# Ventouse.net
KiCad netlist of a schematic drawn in EAGLE
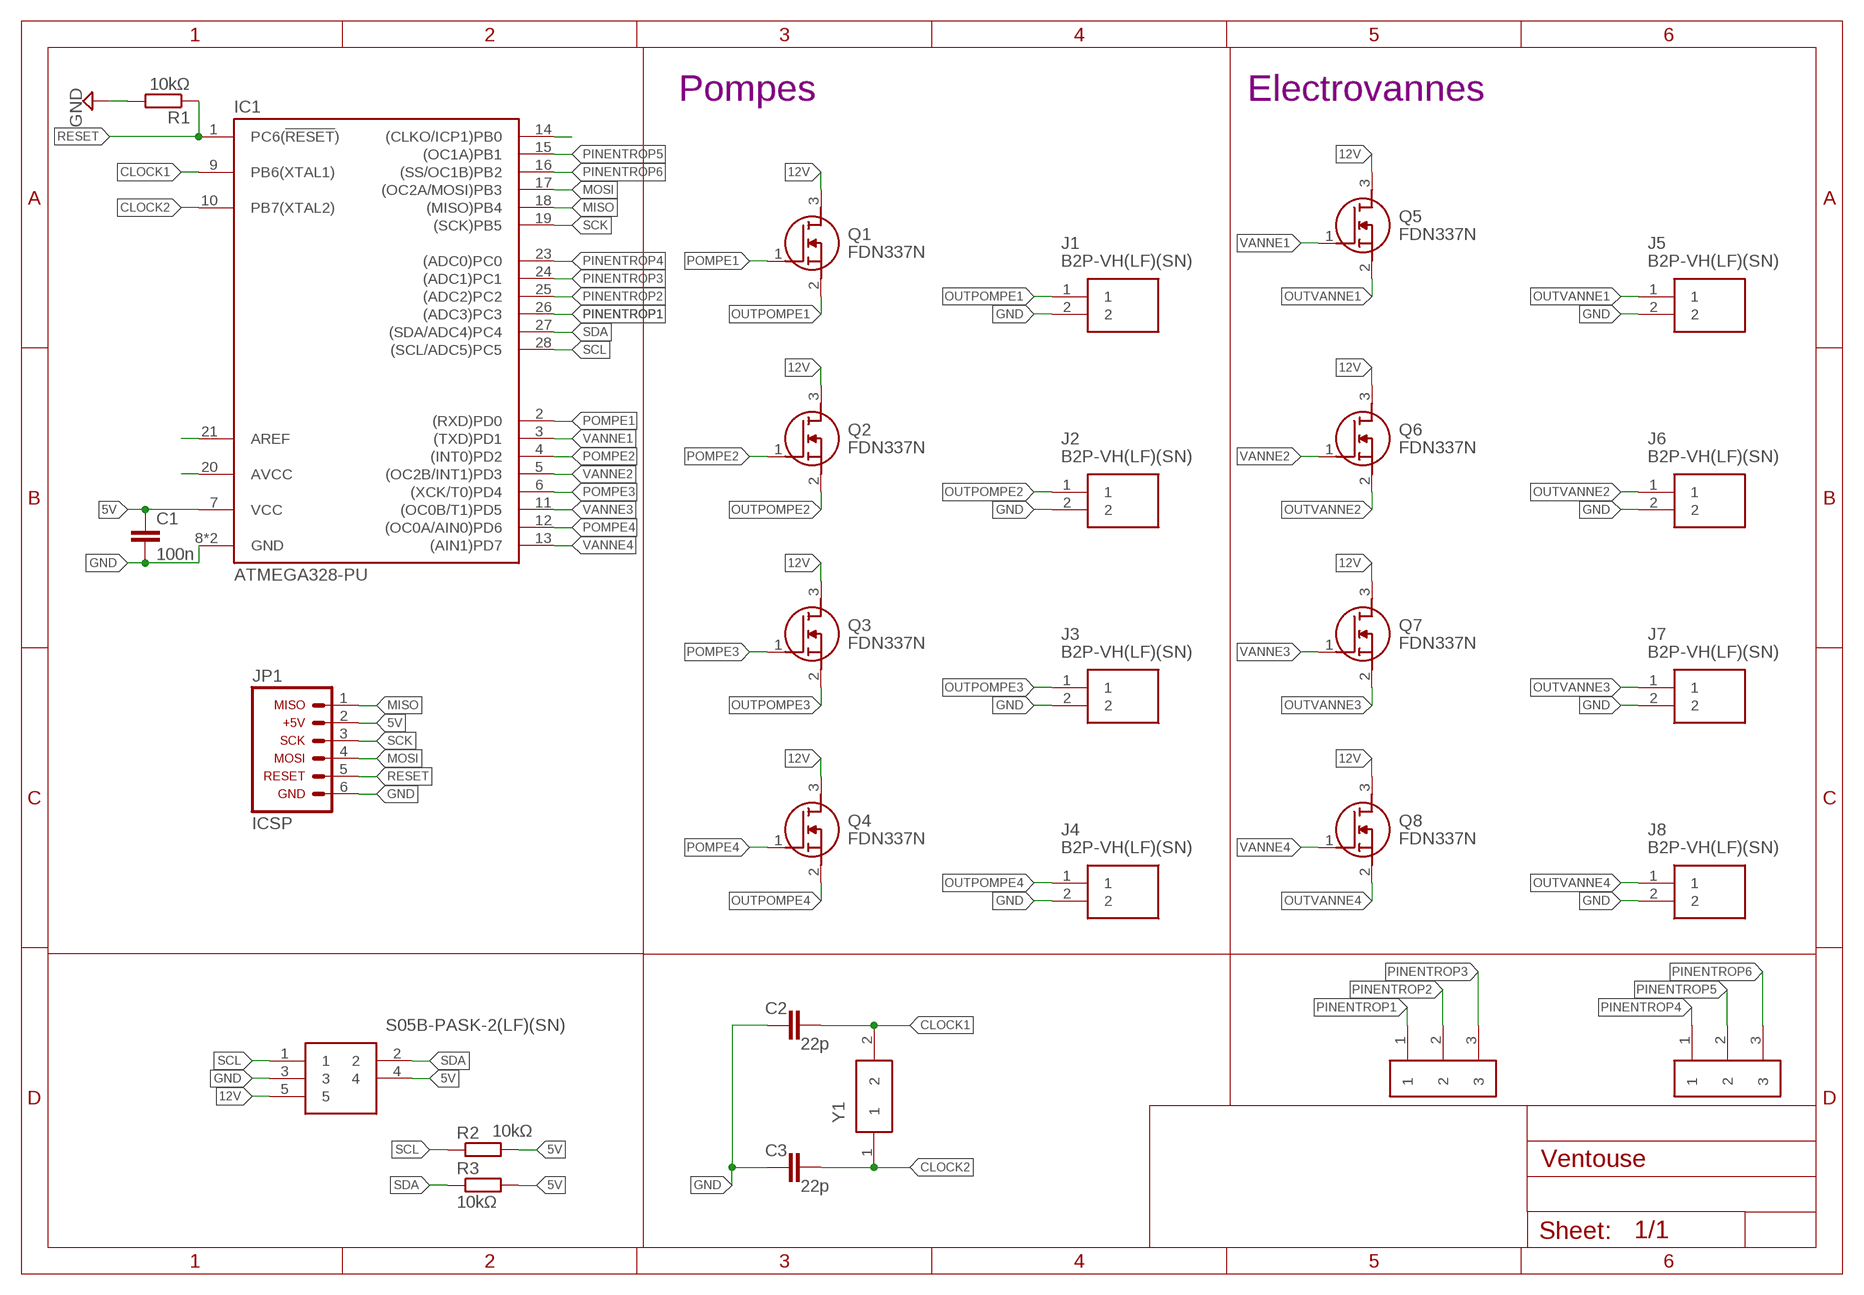
[diagram p0: schematic, sheet 1]

(export (version "E")
  (design (tool "Eeschema 10.0.6"))
  (components
    (comp (ref "C1")
      (value "100n")
      (footprint "eagle-import:C0805")
      (libsource (lib "eagle-import") (part "C-EUC0805"))
    )
    (comp (ref "C2")
      (value "22p")
      (footprint "eagle-import:C0805")
      (libsource (lib "eagle-import") (part "C-EUC0805"))
    )
    (comp (ref "C3")
      (value "22p")
      (footprint "eagle-import:C0805")
      (libsource (lib "eagle-import") (part "C-EUC0805"))
    )
    (comp (ref "IC1")
      (value "ATMEGA328-PU")
      (footprint "eagle-import:DIL28")
      (fields (field (name "MF") "Microchip Technology"))
      (libsource (lib "eagle-import") (part "ATMEGA328-PU"))
    )
    (comp (ref "J1")
      (value "B2P-VH(LF)(SN)")
      (footprint "eagle-import:SHDR2W114P0X396_1X2_786X850X94")
      (fields (field (name "RS_PART_NUMBER") "8201147P"))
      (libsource (lib "eagle-import") (part "B2P-VH(LF)(SN)"))
    )
    (comp (ref "J2")
      (value "B2P-VH(LF)(SN)")
      (footprint "eagle-import:SHDR2W114P0X396_1X2_786X850X94")
      (fields (field (name "RS_PART_NUMBER") "8201147P"))
      (libsource (lib "eagle-import") (part "B2P-VH(LF)(SN)"))
    )
    (comp (ref "J3")
      (value "B2P-VH(LF)(SN)")
      (footprint "eagle-import:SHDR2W114P0X396_1X2_786X850X94")
      (fields (field (name "RS_PART_NUMBER") "8201147P"))
      (libsource (lib "eagle-import") (part "B2P-VH(LF)(SN)"))
    )
    (comp (ref "J4")
      (value "B2P-VH(LF)(SN)")
      (footprint "eagle-import:SHDR2W114P0X396_1X2_786X850X94")
      (fields (field (name "RS_PART_NUMBER") "8201147P"))
      (libsource (lib "eagle-import") (part "B2P-VH(LF)(SN)"))
    )
    (comp (ref "J5")
      (value "B2P-VH(LF)(SN)")
      (footprint "eagle-import:SHDR2W114P0X396_1X2_786X850X94")
      (fields (field (name "RS_PART_NUMBER") "8201147P"))
      (libsource (lib "eagle-import") (part "B2P-VH(LF)(SN)"))
    )
    (comp (ref "J6")
      (value "B2P-VH(LF)(SN)")
      (footprint "eagle-import:SHDR2W114P0X396_1X2_786X850X94")
      (fields (field (name "RS_PART_NUMBER") "8201147P"))
      (libsource (lib "eagle-import") (part "B2P-VH(LF)(SN)"))
    )
    (comp (ref "J7")
      (value "B2P-VH(LF)(SN)")
      (footprint "eagle-import:SHDR2W114P0X396_1X2_786X850X94")
      (fields (field (name "RS_PART_NUMBER") "8201147P"))
      (libsource (lib "eagle-import") (part "B2P-VH(LF)(SN)"))
    )
    (comp (ref "J8")
      (value "B2P-VH(LF)(SN)")
      (footprint "eagle-import:SHDR2W114P0X396_1X2_786X850X94")
      (fields (field (name "RS_PART_NUMBER") "8201147P"))
      (libsource (lib "eagle-import") (part "B2P-VH(LF)(SN)"))
    )
    (comp (ref "JP1")
      (value "ARDUINO_CONN-ICSP")
      (footprint "eagle-import:CONN-2X03")
      (libsource (lib "eagle-import") (part "ARDUINO_CONN-ICSP"))
    )
    (comp (ref "Q1")
      (value "FDN337N")
      (footprint "eagle-import:SOT95P237X112-3N")
      (fields (field (name "MOUSER_PART_NUMBER") "512-FDN337N") (field (name "RS_PART_NUMBER") "6710429P"))
      (libsource (lib "eagle-import") (part "FDN337N"))
    )
    (comp (ref "Q2")
      (value "FDN337N")
      (footprint "eagle-import:SOT95P237X112-3N")
      (fields (field (name "MOUSER_PART_NUMBER") "512-FDN337N") (field (name "RS_PART_NUMBER") "6710429P"))
      (libsource (lib "eagle-import") (part "FDN337N"))
    )
    (comp (ref "Q3")
      (value "FDN337N")
      (footprint "eagle-import:SOT95P237X112-3N")
      (fields (field (name "MOUSER_PART_NUMBER") "512-FDN337N") (field (name "RS_PART_NUMBER") "6710429P"))
      (libsource (lib "eagle-import") (part "FDN337N"))
    )
    (comp (ref "Q4")
      (value "FDN337N")
      (footprint "eagle-import:SOT95P237X112-3N")
      (fields (field (name "MOUSER_PART_NUMBER") "512-FDN337N") (field (name "RS_PART_NUMBER") "6710429P"))
      (libsource (lib "eagle-import") (part "FDN337N"))
    )
    (comp (ref "Q5")
      (value "FDN337N")
      (footprint "eagle-import:SOT95P237X112-3N")
      (fields (field (name "MOUSER_PART_NUMBER") "512-FDN337N") (field (name "RS_PART_NUMBER") "6710429P"))
      (libsource (lib "eagle-import") (part "FDN337N"))
    )
    (comp (ref "Q6")
      (value "FDN337N")
      (footprint "eagle-import:SOT95P237X112-3N")
      (fields (field (name "MOUSER_PART_NUMBER") "512-FDN337N") (field (name "RS_PART_NUMBER") "6710429P"))
      (libsource (lib "eagle-import") (part "FDN337N"))
    )
    (comp (ref "Q7")
      (value "FDN337N")
      (footprint "eagle-import:SOT95P237X112-3N")
      (fields (field (name "MOUSER_PART_NUMBER") "512-FDN337N") (field (name "RS_PART_NUMBER") "6710429P"))
      (libsource (lib "eagle-import") (part "FDN337N"))
    )
    (comp (ref "Q8")
      (value "FDN337N")
      (footprint "eagle-import:SOT95P237X112-3N")
      (fields (field (name "MOUSER_PART_NUMBER") "512-FDN337N") (field (name "RS_PART_NUMBER") "6710429P"))
      (libsource (lib "eagle-import") (part "FDN337N"))
    )
    (comp (ref "R1")
      (value "10kΩ")
      (footprint "eagle-import:R0805")
      (libsource (lib "eagle-import") (part "R-EU_R0805"))
    )
    (comp (ref "R2")
      (value "10kΩ")
      (footprint "eagle-import:R0805")
      (libsource (lib "eagle-import") (part "R-EU_R0805"))
    )
    (comp (ref "R3")
      (value "10kΩ")
      (footprint "eagle-import:R0805")
      (libsource (lib "eagle-import") (part "R-EU_R0805"))
    )
    (comp (ref "SCL")
      (value "S05B-PASK-2(LF)(SN)")
      (footprint "eagle-import:S05B-PASK-2(LF)(SN)")
      (libsource (lib "eagle-import") (part "S05B-PASK-2(LF)(SN)"))
    )
    (comp (ref "U$1")
      (value "HEADER3PIN")
      (footprint "eagle-import:HEADER3PINFOOTPRINT")
      (libsource (lib "eagle-import") (part "HEADER3PIN"))
    )
    (comp (ref "U$2")
      (value "HEADER3PIN")
      (footprint "eagle-import:HEADER3PINFOOTPRINT")
      (libsource (lib "eagle-import") (part "HEADER3PIN"))
    )
    (comp (ref "Y1")
      (value "XRCHA16M000F0A01R0")
      (footprint "eagle-import:XRCHA")
      (fields
        (field (name "MOUSER_PART_NUMBER") "81-XRCHA16M000F0A1R0")
        (field (name "RS_PART_NUMBER") "1446622")
      )
      (libsource (lib "eagle-import") (part "XRCHA16M000F0A01R0"))
    )
  )
  (nets
    (net (code "1") (name "5V") (class "Default")
      (node (ref "C1") (pin "1") (pinfunction "1_1") (pintype "passive"))
      (node (ref "IC1") (pin "7") (pinfunction "VCC_7") (pintype "power_in"))
      (node (ref "JP1") (pin "2") (pinfunction "2_2") (pintype "passive"))
      (node (ref "R2") (pin "2") (pinfunction "2_2") (pintype "passive"))
      (node (ref "R3") (pin "2") (pinfunction "2_2") (pintype "passive"))
      (node (ref "SCL") (pin "4") (pinfunction "4_4") (pintype "bidirectional"))
    )
    (net (code "2") (name "12V") (class "Default")
      (node (ref "Q1") (pin "3") (pinfunction "D_3") (pintype "bidirectional"))
      (node (ref "Q2") (pin "3") (pinfunction "D_3") (pintype "bidirectional"))
      (node (ref "Q3") (pin "3") (pinfunction "D_3") (pintype "bidirectional"))
      (node (ref "Q4") (pin "3") (pinfunction "D_3") (pintype "bidirectional"))
      (node (ref "Q5") (pin "3") (pinfunction "D_3") (pintype "bidirectional"))
      (node (ref "Q6") (pin "3") (pinfunction "D_3") (pintype "bidirectional"))
      (node (ref "Q7") (pin "3") (pinfunction "D_3") (pintype "bidirectional"))
      (node (ref "Q8") (pin "3") (pinfunction "D_3") (pintype "bidirectional"))
      (node (ref "SCL") (pin "5") (pinfunction "5_5") (pintype "bidirectional"))
    )
    (net (code "3") (name "CLOCK1") (class "Default")
      (node (ref "C2") (pin "2") (pinfunction "2_2") (pintype "passive"))
      (node (ref "IC1") (pin "9") (pinfunction "PB6(XTAL1)_9") (pintype "bidirectional"))
      (node (ref "Y1") (pin "2") (pinfunction "2_2") (pintype "bidirectional"))
    )
    (net (code "4") (name "CLOCK2") (class "Default")
      (node (ref "C3") (pin "2") (pinfunction "2_2") (pintype "passive"))
      (node (ref "IC1") (pin "10") (pinfunction "PB7(XTAL2)_10") (pintype "bidirectional"))
      (node (ref "Y1") (pin "1") (pinfunction "1_1") (pintype "bidirectional"))
    )
    (net (code "5") (name "GND") (class "Default")
      (node (ref "C1") (pin "2") (pinfunction "2_2") (pintype "passive"))
      (node (ref "C2") (pin "1") (pinfunction "1_1") (pintype "passive"))
      (node (ref "C3") (pin "1") (pinfunction "1_1") (pintype "passive"))
      (node (ref "IC1") (pin "22") (pinfunction "GND_22") (pintype "power_in"))
      (node (ref "IC1") (pin "8") (pinfunction "GND_8") (pintype "power_in"))
      (node (ref "J1") (pin "2") (pinfunction "2_2") (pintype "bidirectional"))
      (node (ref "J2") (pin "2") (pinfunction "2_2") (pintype "bidirectional"))
      (node (ref "J3") (pin "2") (pinfunction "2_2") (pintype "bidirectional"))
      (node (ref "J4") (pin "2") (pinfunction "2_2") (pintype "bidirectional"))
      (node (ref "J5") (pin "2") (pinfunction "2_2") (pintype "bidirectional"))
      (node (ref "J6") (pin "2") (pinfunction "2_2") (pintype "bidirectional"))
      (node (ref "J7") (pin "2") (pinfunction "2_2") (pintype "bidirectional"))
      (node (ref "J8") (pin "2") (pinfunction "2_2") (pintype "bidirectional"))
      (node (ref "JP1") (pin "6") (pinfunction "6_6") (pintype "passive"))
      (node (ref "R1") (pin "2") (pinfunction "2_2") (pintype "passive"))
      (node (ref "SCL") (pin "3") (pinfunction "3_3") (pintype "bidirectional"))
    )
    (net (code "6") (name "MISO") (class "Default")
      (node (ref "IC1") (pin "18") (pinfunction "(MISO)PB4_18") (pintype "bidirectional"))
      (node (ref "JP1") (pin "1") (pinfunction "1_1") (pintype "passive"))
    )
    (net (code "7") (name "MOSI") (class "Default")
      (node (ref "IC1") (pin "17") (pinfunction "(OC2A/MOSI)PB3_17") (pintype "bidirectional"))
      (node (ref "JP1") (pin "4") (pinfunction "4_4") (pintype "passive"))
    )
    (net (code "8") (name "OUTPOMPE1") (class "Default")
      (node (ref "J1") (pin "1") (pinfunction "1_1") (pintype "bidirectional"))
      (node (ref "Q1") (pin "2") (pinfunction "S_2") (pintype "bidirectional"))
    )
    (net (code "9") (name "OUTPOMPE2") (class "Default")
      (node (ref "J2") (pin "1") (pinfunction "1_1") (pintype "bidirectional"))
      (node (ref "Q2") (pin "2") (pinfunction "S_2") (pintype "bidirectional"))
    )
    (net (code "10") (name "OUTPOMPE3") (class "Default")
      (node (ref "J3") (pin "1") (pinfunction "1_1") (pintype "bidirectional"))
      (node (ref "Q3") (pin "2") (pinfunction "S_2") (pintype "bidirectional"))
    )
    (net (code "11") (name "OUTPOMPE4") (class "Default")
      (node (ref "J4") (pin "1") (pinfunction "1_1") (pintype "bidirectional"))
      (node (ref "Q4") (pin "2") (pinfunction "S_2") (pintype "bidirectional"))
    )
    (net (code "12") (name "OUTVANNE1") (class "Default")
      (node (ref "J5") (pin "1") (pinfunction "1_1") (pintype "bidirectional"))
      (node (ref "Q5") (pin "2") (pinfunction "S_2") (pintype "bidirectional"))
    )
    (net (code "13") (name "OUTVANNE2") (class "Default")
      (node (ref "J6") (pin "1") (pinfunction "1_1") (pintype "bidirectional"))
      (node (ref "Q6") (pin "2") (pinfunction "S_2") (pintype "bidirectional"))
    )
    (net (code "14") (name "OUTVANNE3") (class "Default")
      (node (ref "J7") (pin "1") (pinfunction "1_1") (pintype "bidirectional"))
      (node (ref "Q7") (pin "2") (pinfunction "S_2") (pintype "bidirectional"))
    )
    (net (code "15") (name "OUTVANNE4") (class "Default")
      (node (ref "J8") (pin "1") (pinfunction "1_1") (pintype "bidirectional"))
      (node (ref "Q8") (pin "2") (pinfunction "S_2") (pintype "bidirectional"))
    )
    (net (code "16") (name "PINENTROP1") (class "Default")
      (node (ref "IC1") (pin "26") (pinfunction "(ADC3)PC3_26") (pintype "bidirectional"))
      (node (ref "U$1") (pin "1") (pinfunction "1_1") (pintype "bidirectional"))
    )
    (net (code "17") (name "PINENTROP2") (class "Default")
      (node (ref "IC1") (pin "25") (pinfunction "(ADC2)PC2_25") (pintype "bidirectional"))
      (node (ref "U$1") (pin "2") (pinfunction "2_2") (pintype "bidirectional"))
    )
    (net (code "18") (name "PINENTROP3") (class "Default")
      (node (ref "IC1") (pin "24") (pinfunction "(ADC1)PC1_24") (pintype "bidirectional"))
      (node (ref "U$1") (pin "3") (pinfunction "3_3") (pintype "bidirectional"))
    )
    (net (code "19") (name "PINENTROP4") (class "Default")
      (node (ref "IC1") (pin "23") (pinfunction "(ADC0)PC0_23") (pintype "bidirectional"))
      (node (ref "U$2") (pin "1") (pinfunction "1_1") (pintype "bidirectional"))
    )
    (net (code "20") (name "PINENTROP5") (class "Default")
      (node (ref "IC1") (pin "15") (pinfunction "(OC1A)PB1_15") (pintype "bidirectional"))
      (node (ref "IC1") (pin "21") (pinfunction "AREF_21") (pintype "passive"))
      (node (ref "U$2") (pin "2") (pinfunction "2_2") (pintype "bidirectional"))
    )
    (net (code "21") (name "PINENTROP6") (class "Default")
      (node (ref "IC1") (pin "16") (pinfunction "(SS/OC1B)PB2_16") (pintype "bidirectional"))
      (node (ref "IC1") (pin "20") (pinfunction "AVCC_20") (pintype "power_in"))
      (node (ref "U$2") (pin "3") (pinfunction "3_3") (pintype "bidirectional"))
    )
    (net (code "22") (name "POMPE1") (class "Default")
      (node (ref "IC1") (pin "2") (pinfunction "(RXD)PD0_2") (pintype "bidirectional"))
      (node (ref "Q1") (pin "1") (pinfunction "G_1") (pintype "bidirectional"))
    )
    (net (code "23") (name "POMPE2") (class "Default")
      (node (ref "IC1") (pin "4") (pinfunction "(INT0)PD2_4") (pintype "bidirectional"))
      (node (ref "Q2") (pin "1") (pinfunction "G_1") (pintype "bidirectional"))
    )
    (net (code "24") (name "POMPE3") (class "Default")
      (node (ref "IC1") (pin "6") (pinfunction "(XCK/T0)PD4_6") (pintype "bidirectional"))
      (node (ref "Q3") (pin "1") (pinfunction "G_1") (pintype "bidirectional"))
    )
    (net (code "25") (name "POMPE4") (class "Default")
      (node (ref "IC1") (pin "12") (pinfunction "(OC0A/AIN0)PD6_12") (pintype "bidirectional"))
      (node (ref "Q4") (pin "1") (pinfunction "G_1") (pintype "bidirectional"))
    )
    (net (code "26") (name "RESET") (class "Default")
      (node (ref "IC1") (pin "1") (pinfunction "PC6(~{RESET})_1") (pintype "bidirectional"))
      (node (ref "JP1") (pin "5") (pinfunction "5_5") (pintype "passive"))
      (node (ref "R1") (pin "1") (pinfunction "1_1") (pintype "passive"))
    )
    (net (code "27") (name "SCK") (class "Default")
      (node (ref "IC1") (pin "19") (pinfunction "(SCK)PB5_19") (pintype "bidirectional"))
      (node (ref "JP1") (pin "3") (pinfunction "3_3") (pintype "passive"))
    )
    (net (code "28") (name "SCL") (class "Default")
      (node (ref "IC1") (pin "28") (pinfunction "(SCL/ADC5)PC5_28") (pintype "bidirectional"))
      (node (ref "R2") (pin "1") (pinfunction "1_1") (pintype "passive"))
      (node (ref "SCL") (pin "1") (pinfunction "1_1") (pintype "bidirectional"))
    )
    (net (code "29") (name "SDA") (class "Default")
      (node (ref "IC1") (pin "27") (pinfunction "(SDA/ADC4)PC4_27") (pintype "bidirectional"))
      (node (ref "R3") (pin "1") (pinfunction "1_1") (pintype "passive"))
      (node (ref "SCL") (pin "2") (pinfunction "2_2") (pintype "bidirectional"))
    )
    (net (code "30") (name "VANNE1") (class "Default")
      (node (ref "IC1") (pin "3") (pinfunction "(TXD)PD1_3") (pintype "bidirectional"))
      (node (ref "Q5") (pin "1") (pinfunction "G_1") (pintype "bidirectional"))
    )
    (net (code "31") (name "VANNE2") (class "Default")
      (node (ref "IC1") (pin "5") (pinfunction "(OC2B/INT1)PD3_5") (pintype "bidirectional"))
      (node (ref "Q6") (pin "1") (pinfunction "G_1") (pintype "bidirectional"))
    )
    (net (code "32") (name "VANNE3") (class "Default")
      (node (ref "IC1") (pin "11") (pinfunction "(OC0B/T1)PD5_11") (pintype "bidirectional"))
      (node (ref "Q7") (pin "1") (pinfunction "G_1") (pintype "bidirectional"))
    )
    (net (code "33") (name "VANNE4") (class "Default")
      (node (ref "IC1") (pin "13") (pinfunction "(AIN1)PD7_13") (pintype "bidirectional"))
      (node (ref "Q8") (pin "1") (pinfunction "G_1") (pintype "bidirectional"))
    )
    (net (code "34") (name "unconnected-(IC1-(CLKO{slash}ICP1)PB0-Pad14)") (class "Default")
      (node (ref "IC1") (pin "14") (pinfunction "(CLKO/ICP1)PB0_14") (pintype "bidirectional"))
    )
  )
)
